# light-switch.net
KiCad netlist of a schematic drawn in EAGLE
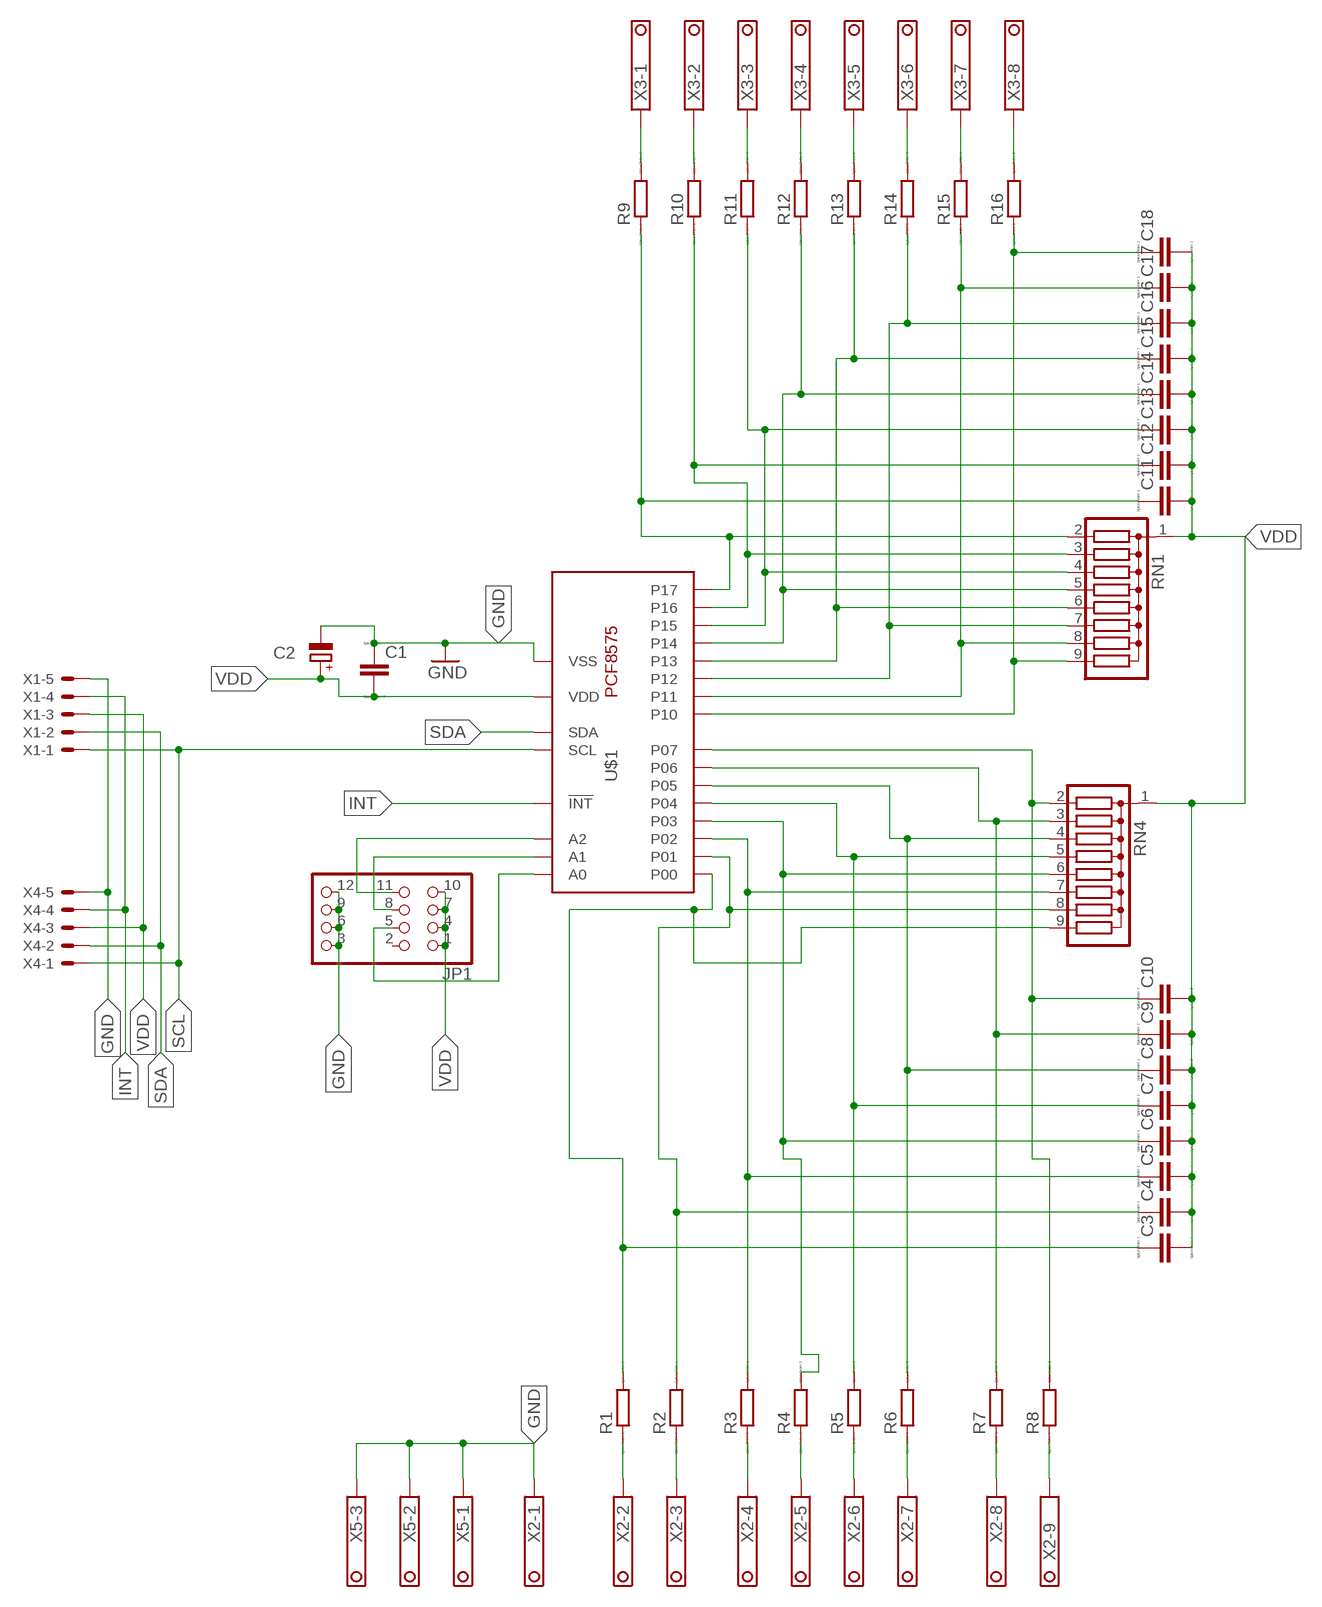
[diagram p0: schematic, sheet 1]

(export (version "E")
  (design (tool "Eeschema 10.0.6"))
  (components
    (comp (ref "C1")
      (value "CC1206")
      (footprint "eagle-import:C1206")
      (libsource (lib "eagle-import") (part "CC1206"))
    )
    (comp (ref "C2")
      (value "CPOL-EU150CLZ-0810")
      (footprint "eagle-import:150CLZ-0810")
      (libsource (lib "eagle-import") (part "CPOL-EU150CLZ-0810"))
    )
    (comp (ref "C3") (value "C") (footprint "eagle-import:C0805") (libsource (lib "eagle-import") (part "C")))
    (comp (ref "C4") (value "C") (footprint "eagle-import:C0805") (libsource (lib "eagle-import") (part "C")))
    (comp (ref "C5") (value "C") (footprint "eagle-import:C0805") (libsource (lib "eagle-import") (part "C")))
    (comp (ref "C6") (value "C") (footprint "eagle-import:C0805") (libsource (lib "eagle-import") (part "C")))
    (comp (ref "C7") (value "C") (footprint "eagle-import:C0805") (libsource (lib "eagle-import") (part "C")))
    (comp (ref "C8") (value "C") (footprint "eagle-import:C0805") (libsource (lib "eagle-import") (part "C")))
    (comp (ref "C9") (value "C") (footprint "eagle-import:C0805") (libsource (lib "eagle-import") (part "C")))
    (comp (ref "C10")
      (value "C")
      (footprint "eagle-import:C0805")
      (libsource (lib "eagle-import") (part "C"))
    )
    (comp (ref "C11")
      (value "C")
      (footprint "eagle-import:C0805")
      (libsource (lib "eagle-import") (part "C"))
    )
    (comp (ref "C12")
      (value "C")
      (footprint "eagle-import:C0805")
      (libsource (lib "eagle-import") (part "C"))
    )
    (comp (ref "C13")
      (value "C")
      (footprint "eagle-import:C0805")
      (libsource (lib "eagle-import") (part "C"))
    )
    (comp (ref "C14")
      (value "C")
      (footprint "eagle-import:C0805")
      (libsource (lib "eagle-import") (part "C"))
    )
    (comp (ref "C15")
      (value "C")
      (footprint "eagle-import:C0805")
      (libsource (lib "eagle-import") (part "C"))
    )
    (comp (ref "C16")
      (value "C")
      (footprint "eagle-import:C0805")
      (libsource (lib "eagle-import") (part "C"))
    )
    (comp (ref "C17")
      (value "C")
      (footprint "eagle-import:C0805")
      (libsource (lib "eagle-import") (part "C"))
    )
    (comp (ref "C18")
      (value "C")
      (footprint "eagle-import:C0805")
      (libsource (lib "eagle-import") (part "C"))
    )
    (comp (ref "JP1")
      (value "PINHD-3X4")
      (footprint "eagle-import:3X04")
      (libsource (lib "eagle-import") (part "PINHD-3X4"))
    )
    (comp (ref "R1")
      (value "RR1206")
      (footprint "eagle-import:R1206")
      (libsource (lib "eagle-import") (part "RR1206"))
    )
    (comp (ref "R2")
      (value "RR1206")
      (footprint "eagle-import:R1206")
      (libsource (lib "eagle-import") (part "RR1206"))
    )
    (comp (ref "R3")
      (value "RR1206")
      (footprint "eagle-import:R1206")
      (libsource (lib "eagle-import") (part "RR1206"))
    )
    (comp (ref "R4")
      (value "RR1206")
      (footprint "eagle-import:R1206")
      (libsource (lib "eagle-import") (part "RR1206"))
    )
    (comp (ref "R5")
      (value "RR1206")
      (footprint "eagle-import:R1206")
      (libsource (lib "eagle-import") (part "RR1206"))
    )
    (comp (ref "R6")
      (value "RR1206")
      (footprint "eagle-import:R1206")
      (libsource (lib "eagle-import") (part "RR1206"))
    )
    (comp (ref "R7")
      (value "RR1206")
      (footprint "eagle-import:R1206")
      (libsource (lib "eagle-import") (part "RR1206"))
    )
    (comp (ref "R8")
      (value "RR1206")
      (footprint "eagle-import:R1206")
      (libsource (lib "eagle-import") (part "RR1206"))
    )
    (comp (ref "R9")
      (value "RR1206")
      (footprint "eagle-import:R1206")
      (libsource (lib "eagle-import") (part "RR1206"))
    )
    (comp (ref "R10")
      (value "RR1206")
      (footprint "eagle-import:R1206")
      (libsource (lib "eagle-import") (part "RR1206"))
    )
    (comp (ref "R11")
      (value "RR1206")
      (footprint "eagle-import:R1206")
      (libsource (lib "eagle-import") (part "RR1206"))
    )
    (comp (ref "R12")
      (value "RR1206")
      (footprint "eagle-import:R1206")
      (libsource (lib "eagle-import") (part "RR1206"))
    )
    (comp (ref "R13")
      (value "RR1206")
      (footprint "eagle-import:R1206")
      (libsource (lib "eagle-import") (part "RR1206"))
    )
    (comp (ref "R14")
      (value "RR1206")
      (footprint "eagle-import:R1206")
      (libsource (lib "eagle-import") (part "RR1206"))
    )
    (comp (ref "R15")
      (value "RR1206")
      (footprint "eagle-import:R1206")
      (libsource (lib "eagle-import") (part "RR1206"))
    )
    (comp (ref "R16")
      (value "RR1206")
      (footprint "eagle-import:R1206")
      (libsource (lib "eagle-import") (part "RR1206"))
    )
    (comp (ref "RN1")
      (value "G08R")
      (footprint "eagle-import:SIL9")
      (libsource (lib "eagle-import") (part "G08R"))
    )
    (comp (ref "RN4")
      (value "G08R")
      (footprint "eagle-import:SIL9")
      (libsource (lib "eagle-import") (part "G08R"))
    )
    (comp (ref "U$1")
      (value "PCF8575CSSOP24")
      (footprint "eagle-import:SOP65P775X200-24N")
      (libsource (lib "eagle-import") (part "PCF8575CSSOP24"))
    )
    (comp (ref "X1")
      (value "JST-XH-05-PIN-LONG-PAD")
      (footprint "eagle-import:JST-XH-05-PACKAGE-LONG-PAD")
      (libsource (lib "eagle-import") (part "JST-XH-05-PIN-LONG-PAD"))
    )
    (comp (ref "X2")
      (value "TERMINAL-BLOCK-3.5MM-9-PIN-LONG-PAD")
      (footprint "eagle-import:TERMINAL-BLOCK-9-PIN-3.5MM-LONG-PAD")
      (libsource (lib "eagle-import") (part "TERMINAL-BLOCK-3.5MM-9-PIN-LONG-PAD"))
    )
    (comp (ref "X3")
      (value "TERMINAL-BLOCK-3.5MM-8-PIN-LONG-PAD")
      (footprint "eagle-import:TERMINAL-BLOCK-8-PIN-3.5MM-LONG-PAD")
      (libsource (lib "eagle-import") (part "TERMINAL-BLOCK-3.5MM-8-PIN-LONG-PAD"))
    )
    (comp (ref "X4")
      (value "JST-XH-05-PIN-LONG-PAD")
      (footprint "eagle-import:JST-XH-05-PACKAGE-LONG-PAD")
      (libsource (lib "eagle-import") (part "JST-XH-05-PIN-LONG-PAD"))
    )
    (comp (ref "X5")
      (value "TERMINAL-BLOCK-3.5MM-3-PIN-LONG-PAD")
      (footprint "eagle-import:TERMINAL-BLOCK-3-PIN-3.5MM-LONG-PAD")
      (libsource (lib "eagle-import") (part "TERMINAL-BLOCK-3.5MM-3-PIN-LONG-PAD"))
    )
  )
  (nets
    (net (code "1") (name "GND") (class "Default")
      (node (ref "C1") (pin "1") (pinfunction "1_1") (pintype "passive"))
      (node (ref "C2") (pin "-") (pinfunction "-_-") (pintype "passive"))
      (node (ref "JP1") (pin "12") (pinfunction "12_12") (pintype "passive"))
      (node (ref "JP1") (pin "3") (pinfunction "3_3") (pintype "passive"))
      (node (ref "JP1") (pin "6") (pinfunction "6_6") (pintype "passive"))
      (node (ref "JP1") (pin "9") (pinfunction "9_9") (pintype "passive"))
      (node (ref "U$1") (pin "12") (pinfunction "VSS_12") (pintype "power_in"))
      (node (ref "X1") (pin "5") (pinfunction "S_5") (pintype "passive"))
      (node (ref "X2") (pin "1") (pinfunction "K_1") (pintype "passive"))
      (node (ref "X4") (pin "5") (pinfunction "S_5") (pintype "passive"))
      (node (ref "X5") (pin "1") (pinfunction "K_1") (pintype "passive"))
      (node (ref "X5") (pin "2") (pinfunction "K_2") (pintype "passive"))
      (node (ref "X5") (pin "3") (pinfunction "K_3") (pintype "passive"))
    )
    (net (code "2") (name "INT") (class "Default")
      (node (ref "U$1") (pin "1") (pinfunction "~{INT}_1") (pintype "open_collector"))
      (node (ref "X1") (pin "4") (pinfunction "S_4") (pintype "passive"))
      (node (ref "X4") (pin "4") (pinfunction "S_4") (pintype "passive"))
    )
    (net (code "3") (name "Net-(U$1-A0)") (class "Default")
      (node (ref "JP1") (pin "5") (pinfunction "5_5") (pintype "passive"))
      (node (ref "U$1") (pin "21") (pinfunction "A0_21") (pintype "input"))
    )
    (net (code "4") (name "Net-(U$1-A1)") (class "Default")
      (node (ref "JP1") (pin "8") (pinfunction "8_8") (pintype "passive"))
      (node (ref "U$1") (pin "2") (pinfunction "A1_2") (pintype "input"))
    )
    (net (code "5") (name "Net-(U$1-A2)") (class "Default")
      (node (ref "JP1") (pin "11") (pinfunction "11_11") (pintype "passive"))
      (node (ref "U$1") (pin "3") (pinfunction "A2_3") (pintype "input"))
    )
    (net (code "6") (name "Net-(U$1-P00)") (class "Default")
      (node (ref "C3") (pin "1") (pinfunction "1_1") (pintype "passive"))
      (node (ref "R1") (pin "2") (pinfunction "2_2") (pintype "passive"))
      (node (ref "RN4") (pin "9") (pinfunction "9_9") (pintype "passive"))
      (node (ref "U$1") (pin "4") (pinfunction "P00_4") (pintype "bidirectional"))
    )
    (net (code "7") (name "Net-(U$1-P01)") (class "Default")
      (node (ref "C4") (pin "1") (pinfunction "1_1") (pintype "passive"))
      (node (ref "R2") (pin "2") (pinfunction "2_2") (pintype "passive"))
      (node (ref "RN4") (pin "8") (pinfunction "8_8") (pintype "passive"))
      (node (ref "U$1") (pin "5") (pinfunction "P01_5") (pintype "bidirectional"))
    )
    (net (code "8") (name "Net-(U$1-P02)") (class "Default")
      (node (ref "C5") (pin "1") (pinfunction "1_1") (pintype "passive"))
      (node (ref "R3") (pin "2") (pinfunction "2_2") (pintype "passive"))
      (node (ref "RN4") (pin "7") (pinfunction "7_7") (pintype "passive"))
      (node (ref "U$1") (pin "6") (pinfunction "P02_6") (pintype "bidirectional"))
    )
    (net (code "9") (name "Net-(U$1-P03)") (class "Default")
      (node (ref "C6") (pin "1") (pinfunction "1_1") (pintype "passive"))
      (node (ref "R4") (pin "2") (pinfunction "2_2") (pintype "passive"))
      (node (ref "RN4") (pin "6") (pinfunction "6_6") (pintype "passive"))
      (node (ref "U$1") (pin "7") (pinfunction "P03_7") (pintype "bidirectional"))
    )
    (net (code "10") (name "Net-(U$1-P04)") (class "Default")
      (node (ref "C7") (pin "1") (pinfunction "1_1") (pintype "passive"))
      (node (ref "R5") (pin "2") (pinfunction "2_2") (pintype "passive"))
      (node (ref "RN4") (pin "5") (pinfunction "5_5") (pintype "passive"))
      (node (ref "U$1") (pin "8") (pinfunction "P04_8") (pintype "bidirectional"))
    )
    (net (code "11") (name "Net-(U$1-P05)") (class "Default")
      (node (ref "C8") (pin "1") (pinfunction "1_1") (pintype "passive"))
      (node (ref "R6") (pin "2") (pinfunction "2_2") (pintype "passive"))
      (node (ref "RN4") (pin "4") (pinfunction "4_4") (pintype "passive"))
      (node (ref "U$1") (pin "9") (pinfunction "P05_9") (pintype "bidirectional"))
    )
    (net (code "12") (name "Net-(U$1-P06)") (class "Default")
      (node (ref "C9") (pin "1") (pinfunction "1_1") (pintype "passive"))
      (node (ref "R7") (pin "2") (pinfunction "2_2") (pintype "passive"))
      (node (ref "RN4") (pin "3") (pinfunction "3_3") (pintype "passive"))
      (node (ref "U$1") (pin "10") (pinfunction "P06_10") (pintype "bidirectional"))
    )
    (net (code "13") (name "Net-(U$1-P07)") (class "Default")
      (node (ref "C10") (pin "1") (pinfunction "1_1") (pintype "passive"))
      (node (ref "R8") (pin "2") (pinfunction "2_2") (pintype "passive"))
      (node (ref "RN4") (pin "2") (pinfunction "2_2") (pintype "passive"))
      (node (ref "U$1") (pin "11") (pinfunction "P07_11") (pintype "bidirectional"))
    )
    (net (code "14") (name "Net-(U$1-P10)") (class "Default")
      (node (ref "C18") (pin "1") (pinfunction "1_1") (pintype "passive"))
      (node (ref "R16") (pin "1") (pinfunction "1_1") (pintype "passive"))
      (node (ref "RN1") (pin "9") (pinfunction "9_9") (pintype "passive"))
      (node (ref "U$1") (pin "13") (pinfunction "P10_13") (pintype "bidirectional"))
    )
    (net (code "15") (name "Net-(U$1-P11)") (class "Default")
      (node (ref "C17") (pin "1") (pinfunction "1_1") (pintype "passive"))
      (node (ref "R15") (pin "1") (pinfunction "1_1") (pintype "passive"))
      (node (ref "RN1") (pin "8") (pinfunction "8_8") (pintype "passive"))
      (node (ref "U$1") (pin "14") (pinfunction "P11_14") (pintype "bidirectional"))
    )
    (net (code "16") (name "Net-(U$1-P12)") (class "Default")
      (node (ref "C16") (pin "1") (pinfunction "1_1") (pintype "passive"))
      (node (ref "R14") (pin "1") (pinfunction "1_1") (pintype "passive"))
      (node (ref "RN1") (pin "7") (pinfunction "7_7") (pintype "passive"))
      (node (ref "U$1") (pin "15") (pinfunction "P12_15") (pintype "bidirectional"))
    )
    (net (code "17") (name "Net-(U$1-P13)") (class "Default")
      (node (ref "C15") (pin "1") (pinfunction "1_1") (pintype "passive"))
      (node (ref "R13") (pin "1") (pinfunction "1_1") (pintype "passive"))
      (node (ref "RN1") (pin "6") (pinfunction "6_6") (pintype "passive"))
      (node (ref "U$1") (pin "16") (pinfunction "P13_16") (pintype "bidirectional"))
    )
    (net (code "18") (name "Net-(U$1-P14)") (class "Default")
      (node (ref "C14") (pin "1") (pinfunction "1_1") (pintype "passive"))
      (node (ref "R12") (pin "1") (pinfunction "1_1") (pintype "passive"))
      (node (ref "RN1") (pin "5") (pinfunction "5_5") (pintype "passive"))
      (node (ref "U$1") (pin "17") (pinfunction "P14_17") (pintype "bidirectional"))
    )
    (net (code "19") (name "Net-(U$1-P15)") (class "Default")
      (node (ref "C13") (pin "1") (pinfunction "1_1") (pintype "passive"))
      (node (ref "R11") (pin "1") (pinfunction "1_1") (pintype "passive"))
      (node (ref "RN1") (pin "4") (pinfunction "4_4") (pintype "passive"))
      (node (ref "U$1") (pin "18") (pinfunction "P15_18") (pintype "bidirectional"))
    )
    (net (code "20") (name "Net-(U$1-P16)") (class "Default")
      (node (ref "C12") (pin "1") (pinfunction "1_1") (pintype "passive"))
      (node (ref "R10") (pin "1") (pinfunction "1_1") (pintype "passive"))
      (node (ref "RN1") (pin "3") (pinfunction "3_3") (pintype "passive"))
      (node (ref "U$1") (pin "19") (pinfunction "P16_19") (pintype "bidirectional"))
    )
    (net (code "21") (name "Net-(U$1-P17)") (class "Default")
      (node (ref "C11") (pin "1") (pinfunction "1_1") (pintype "passive"))
      (node (ref "R9") (pin "1") (pinfunction "1_1") (pintype "passive"))
      (node (ref "RN1") (pin "2") (pinfunction "2_2") (pintype "passive"))
      (node (ref "U$1") (pin "20") (pinfunction "P17_20") (pintype "bidirectional"))
    )
    (net (code "22") (name "Net-(X2B-K)") (class "Default")
      (node (ref "R1") (pin "1") (pinfunction "1_1") (pintype "passive"))
      (node (ref "X2") (pin "2") (pinfunction "K_2") (pintype "passive"))
    )
    (net (code "23") (name "Net-(X2C-K)") (class "Default")
      (node (ref "R2") (pin "1") (pinfunction "1_1") (pintype "passive"))
      (node (ref "X2") (pin "3") (pinfunction "K_3") (pintype "passive"))
    )
    (net (code "24") (name "Net-(X2D-K)") (class "Default")
      (node (ref "R3") (pin "1") (pinfunction "1_1") (pintype "passive"))
      (node (ref "X2") (pin "4") (pinfunction "K_4") (pintype "passive"))
    )
    (net (code "25") (name "Net-(X2E-K)") (class "Default")
      (node (ref "R4") (pin "1") (pinfunction "1_1") (pintype "passive"))
      (node (ref "X2") (pin "5") (pinfunction "K_5") (pintype "passive"))
    )
    (net (code "26") (name "Net-(X2F-K)") (class "Default")
      (node (ref "R5") (pin "1") (pinfunction "1_1") (pintype "passive"))
      (node (ref "X2") (pin "6") (pinfunction "K_6") (pintype "passive"))
    )
    (net (code "27") (name "Net-(X2G-K)") (class "Default")
      (node (ref "R6") (pin "1") (pinfunction "1_1") (pintype "passive"))
      (node (ref "X2") (pin "7") (pinfunction "K_7") (pintype "passive"))
    )
    (net (code "28") (name "Net-(X2H-K)") (class "Default")
      (node (ref "R7") (pin "1") (pinfunction "1_1") (pintype "passive"))
      (node (ref "X2") (pin "8") (pinfunction "K_8") (pintype "passive"))
    )
    (net (code "29") (name "Net-(X2I-K)") (class "Default")
      (node (ref "R8") (pin "1") (pinfunction "1_1") (pintype "passive"))
      (node (ref "X2") (pin "9") (pinfunction "K_9") (pintype "passive"))
    )
    (net (code "30") (name "Net-(X3A-K)") (class "Default")
      (node (ref "R9") (pin "2") (pinfunction "2_2") (pintype "passive"))
      (node (ref "X3") (pin "1") (pinfunction "K_1") (pintype "passive"))
    )
    (net (code "31") (name "Net-(X3B-K)") (class "Default")
      (node (ref "R10") (pin "2") (pinfunction "2_2") (pintype "passive"))
      (node (ref "X3") (pin "2") (pinfunction "K_2") (pintype "passive"))
    )
    (net (code "32") (name "Net-(X3C-K)") (class "Default")
      (node (ref "R11") (pin "2") (pinfunction "2_2") (pintype "passive"))
      (node (ref "X3") (pin "3") (pinfunction "K_3") (pintype "passive"))
    )
    (net (code "33") (name "Net-(X3D-K)") (class "Default")
      (node (ref "R12") (pin "2") (pinfunction "2_2") (pintype "passive"))
      (node (ref "X3") (pin "4") (pinfunction "K_4") (pintype "passive"))
    )
    (net (code "34") (name "Net-(X3E-K)") (class "Default")
      (node (ref "R13") (pin "2") (pinfunction "2_2") (pintype "passive"))
      (node (ref "X3") (pin "5") (pinfunction "K_5") (pintype "passive"))
    )
    (net (code "35") (name "Net-(X3F-K)") (class "Default")
      (node (ref "R14") (pin "2") (pinfunction "2_2") (pintype "passive"))
      (node (ref "X3") (pin "6") (pinfunction "K_6") (pintype "passive"))
    )
    (net (code "36") (name "Net-(X3G-K)") (class "Default")
      (node (ref "R15") (pin "2") (pinfunction "2_2") (pintype "passive"))
      (node (ref "X3") (pin "7") (pinfunction "K_7") (pintype "passive"))
    )
    (net (code "37") (name "Net-(X3H-K)") (class "Default")
      (node (ref "R16") (pin "2") (pinfunction "2_2") (pintype "passive"))
      (node (ref "X3") (pin "8") (pinfunction "K_8") (pintype "passive"))
    )
    (net (code "38") (name "SCL") (class "Default")
      (node (ref "U$1") (pin "22") (pinfunction "SCL_22") (pintype "input"))
      (node (ref "X1") (pin "1") (pinfunction "S_1") (pintype "passive"))
      (node (ref "X4") (pin "1") (pinfunction "S_1") (pintype "passive"))
    )
    (net (code "39") (name "SDA") (class "Default")
      (node (ref "U$1") (pin "23") (pinfunction "SDA_23") (pintype "bidirectional"))
      (node (ref "X1") (pin "2") (pinfunction "S_2") (pintype "passive"))
      (node (ref "X4") (pin "2") (pinfunction "S_2") (pintype "passive"))
    )
    (net (code "40") (name "VDD") (class "Default")
      (node (ref "C1") (pin "2") (pinfunction "2_2") (pintype "passive"))
      (node (ref "C10") (pin "2") (pinfunction "2_2") (pintype "passive"))
      (node (ref "C11") (pin "2") (pinfunction "2_2") (pintype "passive"))
      (node (ref "C12") (pin "2") (pinfunction "2_2") (pintype "passive"))
      (node (ref "C13") (pin "2") (pinfunction "2_2") (pintype "passive"))
      (node (ref "C14") (pin "2") (pinfunction "2_2") (pintype "passive"))
      (node (ref "C15") (pin "2") (pinfunction "2_2") (pintype "passive"))
      (node (ref "C16") (pin "2") (pinfunction "2_2") (pintype "passive"))
      (node (ref "C17") (pin "2") (pinfunction "2_2") (pintype "passive"))
      (node (ref "C18") (pin "2") (pinfunction "2_2") (pintype "passive"))
      (node (ref "C2") (pin "+") (pinfunction "+_+") (pintype "passive"))
      (node (ref "C3") (pin "2") (pinfunction "2_2") (pintype "passive"))
      (node (ref "C4") (pin "2") (pinfunction "2_2") (pintype "passive"))
      (node (ref "C5") (pin "2") (pinfunction "2_2") (pintype "passive"))
      (node (ref "C6") (pin "2") (pinfunction "2_2") (pintype "passive"))
      (node (ref "C7") (pin "2") (pinfunction "2_2") (pintype "passive"))
      (node (ref "C8") (pin "2") (pinfunction "2_2") (pintype "passive"))
      (node (ref "C9") (pin "2") (pinfunction "2_2") (pintype "passive"))
      (node (ref "JP1") (pin "1") (pinfunction "1_1") (pintype "passive"))
      (node (ref "JP1") (pin "10") (pinfunction "10_10") (pintype "passive"))
      (node (ref "JP1") (pin "4") (pinfunction "4_4") (pintype "passive"))
      (node (ref "JP1") (pin "7") (pinfunction "7_7") (pintype "passive"))
      (node (ref "RN1") (pin "1") (pinfunction "1_1") (pintype "passive"))
      (node (ref "RN4") (pin "1") (pinfunction "1_1") (pintype "passive"))
      (node (ref "U$1") (pin "24") (pinfunction "VDD_24") (pintype "power_in"))
      (node (ref "X1") (pin "3") (pinfunction "S_3") (pintype "passive"))
      (node (ref "X4") (pin "3") (pinfunction "S_3") (pintype "passive"))
    )
    (net (code "41") (name "unconnected-(JP1-Pad2)") (class "Default")
      (node (ref "JP1") (pin "2") (pinfunction "2_2") (pintype "passive"))
    )
  )
)
